# hexbot.net
KiCad netlist of a schematic drawn in Altium Designer
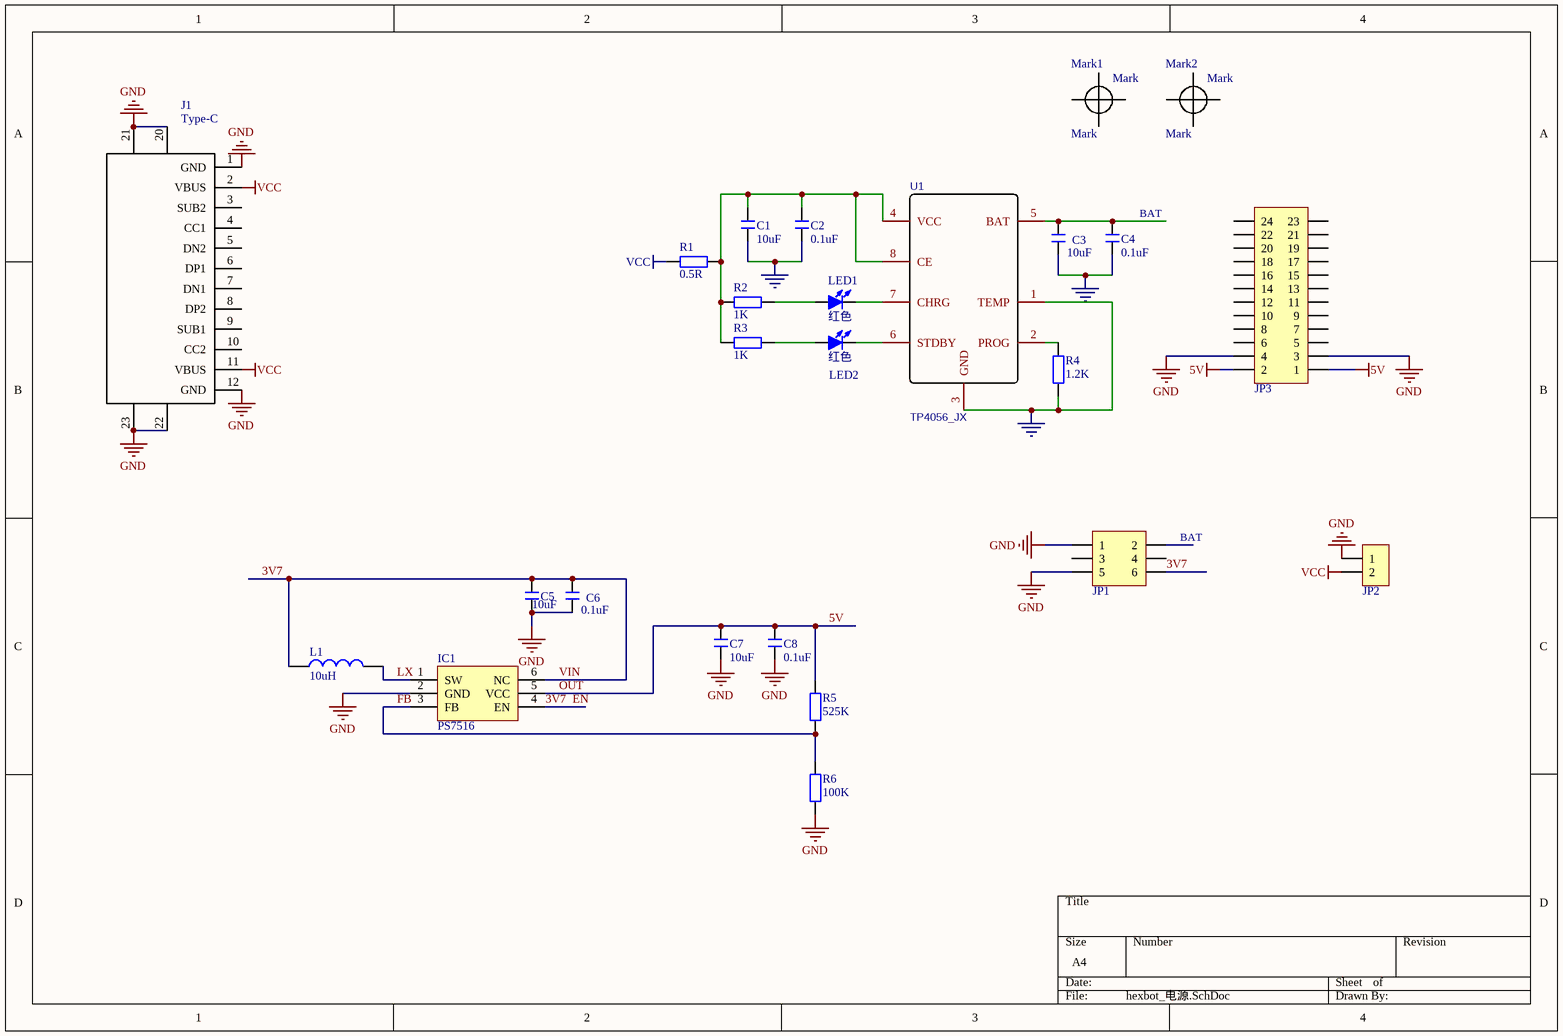
[diagram p0: hexbot_电源.SchDoc]

(export (version "E")
  (design (tool "Eeschema 10.0.6"))
  (components
    (comp (ref "C1")
      (value "10uF")
      (footprint "C 0603_L")
      (description "贴片电容")
      (libsource (lib "0.1 - 电阻-电容-电感") (part "C"))
    )
    (comp (ref "C2")
      (value "0.1uF")
      (footprint "C 0603_L")
      (description "贴片电容")
      (libsource (lib "0.1 - 电阻-电容-电感") (part "C"))
    )
    (comp (ref "C3")
      (value "10uF")
      (footprint "C 0603_L")
      (description "贴片电容")
      (libsource (lib "0.1 - 电阻-电容-电感") (part "C"))
    )
    (comp (ref "C4")
      (value "0.1uF")
      (footprint "C 0603_L")
      (description "贴片电容")
      (libsource (lib "0.1 - 电阻-电容-电感") (part "C"))
    )
    (comp (ref "C5")
      (value "10uF")
      (footprint "C 0603_L")
      (description "贴片电容")
      (libsource (lib "0.1 - 电阻-电容-电感") (part "C"))
    )
    (comp (ref "C6")
      (value "0.1uF")
      (footprint "C 0603_L")
      (description "贴片电容")
      (libsource (lib "0.1 - 电阻-电容-电感") (part "C"))
    )
    (comp (ref "C7")
      (value "10uF")
      (footprint "C 0603_L")
      (description "贴片电容")
      (libsource (lib "0.1 - 电阻-电容-电感") (part "C"))
    )
    (comp (ref "C8")
      (value "0.1uF")
      (footprint "C 0603_L")
      (description "贴片电容")
      (libsource (lib "0.1 - 电阻-电容-电感") (part "C"))
    )
    (comp (ref "IC1")
      (value "PS7516")
      (footprint "SOT23-6L")
      (description "可调升压芯片")
      (fields (field (name "版权归属") "封装库来自淘宝 ID：黄晶宝石"))
      (libsource (lib "1.1 - 电源类芯片") (part "SX1308"))
    )
    (comp (ref "J1")
      (value "Type-C")
      (footprint "Type-C-16")
      (libsource (lib "TYPE-C-16PIN") (part "Type-C-16pin"))
    )
    (comp (ref "JP1")
      (value "Header3X2")
      (footprint "HDR2.54-LI-2x3P")
      (description "3*2P接插件")
      (fields (field (name "版权归属") "封装库来自淘宝 ID：黄晶宝石"))
      (libsource (lib "5.4 - 接插件-脚距2.54 (100mil) ") (part "Header 3X2"))
    )
    (comp (ref "JP2")
      (value "HDR-1X2")
      (footprint "HDR2.54-LI-2P")
      (description "2P接插件")
      (fields (field (name "版权归属") "封装库来自淘宝 ID：黄晶宝石"))
      (libsource (lib "5.4 - 接插件-脚距2.54 (100mil) ") (part "Header 2"))
    )
    (comp (ref "JP3")
      (value "Header 2X11")
      (footprint "HDR2.54-WI-2x12P")
      (description "12*2P接插件")
      (fields (field (name "版权归属") "封装库来自淘宝卖家 ID：黄晶宝石"))
      (libsource (lib "5.4 - 接插件-脚距2.54 (100mil) ") (part "Header 12X2"))
    )
    (comp (ref "L1")
      (value "10uH")
      (footprint "L 0603")
      (description "小功率贴片电感")
      (libsource (lib "0.1 - 电阻-电容-电感") (part "L"))
    )
    (comp (ref "LED1")
      (value "红色")
      (footprint "LED 0603R")
      (description "贴片LED")
      (fields (field (name "版权归属") "封装库来自淘宝 ID：黄晶宝石"))
      (libsource (lib "0.3 - LED发光二极管") (part "LED-SMD"))
    )
    (comp (ref "LED2")
      (value "红色")
      (footprint "LED 0603R")
      (description "贴片LED")
      (fields (field (name "版权归属") "封装库来自淘宝 ID：黄晶宝石"))
      (libsource (lib "0.3 - LED发光二极管") (part "LED-SMD"))
    )
    (comp (ref "Mark1") (value "Mark") (footprint "Mark:Mark") (libsource (lib "Mark") (part "Mark")))
    (comp (ref "Mark2") (value "Mark") (footprint "Mark:Mark") (libsource (lib "Mark") (part "Mark")))
    (comp (ref "R1")
      (value "0.5R")
      (footprint "R 0603_L")
      (description "贴片电阻")
      (fields (field (name "版权归属") "来自淘宝 ID：黄晶宝石"))
      (libsource (lib "0.1 - 电阻-电容-电感") (part "R"))
    )
    (comp (ref "R2")
      (value "1K")
      (footprint "R 0603_L")
      (description "贴片电阻")
      (fields (field (name "版权归属") "来自淘宝 ID：黄晶宝石"))
      (libsource (lib "0.1 - 电阻-电容-电感") (part "R"))
    )
    (comp (ref "R3")
      (value "1K")
      (footprint "R 0603_L")
      (description "贴片电阻")
      (fields (field (name "版权归属") "来自淘宝 ID：黄晶宝石"))
      (libsource (lib "0.1 - 电阻-电容-电感") (part "R"))
    )
    (comp (ref "R4")
      (value "1.2K")
      (footprint "R 0603_L")
      (description "贴片电阻")
      (fields (field (name "版权归属") "来自淘宝 ID：黄晶宝石"))
      (libsource (lib "0.1 - 电阻-电容-电感") (part "R"))
    )
    (comp (ref "R5")
      (value "525K")
      (footprint "R 0805_L")
      (description "贴片电阻")
      (fields (field (name "版权归属") "来自淘宝 ID：黄晶宝石"))
      (libsource (lib "0.1 - 电阻-电容-电感") (part "R"))
    )
    (comp (ref "R6")
      (value "100K")
      (footprint "R 0805_L")
      (description "贴片电阻")
      (fields (field (name "版权归属") "来自淘宝 ID：黄晶宝石"))
      (libsource (lib "0.1 - 电阻-电容-电感") (part "R"))
    )
    (comp (ref "U1") (value "TP4056_JX") (footprint "TP4056") (libsource (lib "TP4056") (part "TP4056_JX")))
  )
  (nets
    (net (code "1") (name "/3V7") (class "Default")
      (node (ref "C5") (pin "2") (pinfunction "2_2") (pintype "passive"))
      (node (ref "C6") (pin "2") (pinfunction "2_2") (pintype "passive"))
      (node (ref "IC1") (pin "4") (pinfunction "EN_4") (pintype "passive"))
      (node (ref "IC1") (pin "6") (pinfunction "NC_6") (pintype "passive"))
      (node (ref "JP1") (pin "6") (pinfunction "6_6") (pintype "passive"))
      (node (ref "L1") (pin "1") (pinfunction "1_1") (pintype "passive"))
    )
    (net (code "2") (name "/BAT") (class "Default")
      (node (ref "C3") (pin "2") (pinfunction "2_2") (pintype "passive"))
      (node (ref "C4") (pin "2") (pinfunction "2_2") (pintype "passive"))
      (node (ref "JP1") (pin "2") (pinfunction "2_2") (pintype "passive"))
      (node (ref "U1") (pin "5") (pinfunction "BAT_5") (pintype "passive"))
    )
    (net (code "3") (name "/FB") (class "Default")
      (node (ref "IC1") (pin "3") (pinfunction "FB_3") (pintype "passive"))
      (node (ref "R5") (pin "1") (pinfunction "1_1") (pintype "passive"))
      (node (ref "R6") (pin "2") (pinfunction "2_2") (pintype "passive"))
    )
    (net (code "4") (name "/LX") (class "Default")
      (node (ref "IC1") (pin "1") (pinfunction "SW_1") (pintype "passive"))
      (node (ref "L1") (pin "2") (pinfunction "2_2") (pintype "passive"))
    )
    (net (code "5") (name "5V") (class "Default")
      (node (ref "C7") (pin "2") (pinfunction "2_2") (pintype "passive"))
      (node (ref "C8") (pin "2") (pinfunction "2_2") (pintype "passive"))
      (node (ref "IC1") (pin "5") (pinfunction "VCC_5") (pintype "passive"))
      (node (ref "JP3") (pin "1") (pinfunction "1_1") (pintype "passive"))
      (node (ref "JP3") (pin "2") (pinfunction "2_2") (pintype "passive"))
      (node (ref "R5") (pin "2") (pinfunction "2_2") (pintype "passive"))
    )
    (net (code "6") (name "GND") (class "Default")
      (node (ref "C1") (pin "1") (pinfunction "1_1") (pintype "passive"))
      (node (ref "C2") (pin "1") (pinfunction "1_1") (pintype "passive"))
      (node (ref "C3") (pin "1") (pinfunction "1_1") (pintype "passive"))
      (node (ref "C4") (pin "1") (pinfunction "1_1") (pintype "passive"))
      (node (ref "C5") (pin "1") (pinfunction "1_1") (pintype "passive"))
      (node (ref "C6") (pin "1") (pinfunction "1_1") (pintype "passive"))
      (node (ref "C7") (pin "1") (pinfunction "1_1") (pintype "passive"))
      (node (ref "C8") (pin "1") (pinfunction "1_1") (pintype "passive"))
      (node (ref "IC1") (pin "2") (pinfunction "GND_2") (pintype "passive"))
      (node (ref "J1") (pin "1") (pinfunction "GND_1") (pintype "passive"))
      (node (ref "J1") (pin "12") (pinfunction "GND_12") (pintype "passive"))
      (node (ref "J1") (pin "20") (pintype "passive"))
      (node (ref "J1") (pin "21") (pintype "passive"))
      (node (ref "J1") (pin "22") (pintype "passive"))
      (node (ref "J1") (pin "23") (pintype "passive"))
      (node (ref "JP1") (pin "1") (pinfunction "1_1") (pintype "passive"))
      (node (ref "JP1") (pin "5") (pinfunction "5_5") (pintype "passive"))
      (node (ref "JP2") (pin "1") (pinfunction "1_1") (pintype "passive"))
      (node (ref "JP3") (pin "3") (pinfunction "3_3") (pintype "passive"))
      (node (ref "JP3") (pin "4") (pinfunction "4_4") (pintype "passive"))
      (node (ref "R4") (pin "1") (pinfunction "1_1") (pintype "passive"))
      (node (ref "R6") (pin "1") (pinfunction "1_1") (pintype "passive"))
      (node (ref "U1") (pin "1") (pinfunction "TEMP_1") (pintype "passive"))
      (node (ref "U1") (pin "3") (pinfunction "GND_3") (pintype "passive"))
    )
    (net (code "7") (name "Net-(LED1-A)") (class "Default")
      (node (ref "LED1") (pin "1") (pinfunction "A_1") (pintype "passive"))
      (node (ref "R2") (pin "2") (pinfunction "2_2") (pintype "passive"))
    )
    (net (code "8") (name "Net-(LED1-K)") (class "Default")
      (node (ref "LED1") (pin "2") (pinfunction "K_2") (pintype "passive"))
      (node (ref "U1") (pin "7") (pinfunction "CHRG_7") (pintype "passive"))
    )
    (net (code "9") (name "Net-(LED2-A)") (class "Default")
      (node (ref "LED2") (pin "1") (pinfunction "A_1") (pintype "passive"))
      (node (ref "R3") (pin "2") (pinfunction "2_2") (pintype "passive"))
    )
    (net (code "10") (name "Net-(LED2-K)") (class "Default")
      (node (ref "LED2") (pin "2") (pinfunction "K_2") (pintype "passive"))
      (node (ref "U1") (pin "6") (pinfunction "STDBY_6") (pintype "passive"))
    )
    (net (code "11") (name "Net-(U1-CE)") (class "Default")
      (node (ref "C1") (pin "2") (pinfunction "2_2") (pintype "passive"))
      (node (ref "C2") (pin "2") (pinfunction "2_2") (pintype "passive"))
      (node (ref "R1") (pin "2") (pinfunction "2_2") (pintype "passive"))
      (node (ref "R2") (pin "1") (pinfunction "1_1") (pintype "passive"))
      (node (ref "R3") (pin "1") (pinfunction "1_1") (pintype "passive"))
      (node (ref "U1") (pin "4") (pinfunction "VCC_4") (pintype "passive"))
      (node (ref "U1") (pin "8") (pinfunction "CE_8") (pintype "passive"))
    )
    (net (code "12") (name "Net-(U1-PROG)") (class "Default")
      (node (ref "R4") (pin "2") (pinfunction "2_2") (pintype "passive"))
      (node (ref "U1") (pin "2") (pinfunction "PROG_2") (pintype "passive"))
    )
    (net (code "13") (name "VCC") (class "Default")
      (node (ref "J1") (pin "11") (pinfunction "VBUS_11") (pintype "passive"))
      (node (ref "J1") (pin "2") (pinfunction "VBUS_2") (pintype "passive"))
      (node (ref "JP2") (pin "2") (pinfunction "2_2") (pintype "passive"))
      (node (ref "R1") (pin "1") (pinfunction "1_1") (pintype "passive"))
    )
    (net (code "14") (name "unconnected-(J1-CC1-Pad4)") (class "Default")
      (node (ref "J1") (pin "4") (pinfunction "CC1_4") (pintype "passive"))
    )
    (net (code "15") (name "unconnected-(J1-CC2-Pad10)") (class "Default")
      (node (ref "J1") (pin "10") (pinfunction "CC2_10") (pintype "passive"))
    )
    (net (code "16") (name "unconnected-(J1-DN1-Pad7)") (class "Default")
      (node (ref "J1") (pin "7") (pinfunction "DN1_7") (pintype "passive"))
    )
    (net (code "17") (name "unconnected-(J1-DN2-Pad5)") (class "Default")
      (node (ref "J1") (pin "5") (pinfunction "DN2_5") (pintype "passive"))
    )
    (net (code "18") (name "unconnected-(J1-DP1-Pad6)") (class "Default")
      (node (ref "J1") (pin "6") (pinfunction "DP1_6") (pintype "passive"))
    )
    (net (code "19") (name "unconnected-(J1-DP2-Pad8)") (class "Default")
      (node (ref "J1") (pin "8") (pinfunction "DP2_8") (pintype "passive"))
    )
    (net (code "20") (name "unconnected-(J1-SUB1-Pad9)") (class "Default")
      (node (ref "J1") (pin "9") (pinfunction "SUB1_9") (pintype "passive"))
    )
    (net (code "21") (name "unconnected-(J1-SUB2-Pad3)") (class "Default")
      (node (ref "J1") (pin "3") (pinfunction "SUB2_3") (pintype "passive"))
    )
    (net (code "22") (name "unconnected-(JP1-Pad3)") (class "Default")
      (node (ref "JP1") (pin "3") (pinfunction "3_3") (pintype "passive"))
    )
    (net (code "23") (name "unconnected-(JP1-Pad4)") (class "Default")
      (node (ref "JP1") (pin "4") (pinfunction "4_4") (pintype "passive"))
    )
    (net (code "24") (name "unconnected-(JP3-Pad5)") (class "Default")
      (node (ref "JP3") (pin "5") (pinfunction "5_5") (pintype "passive"))
    )
    (net (code "25") (name "unconnected-(JP3-Pad6)") (class "Default")
      (node (ref "JP3") (pin "6") (pinfunction "6_6") (pintype "passive"))
    )
    (net (code "26") (name "unconnected-(JP3-Pad7)") (class "Default")
      (node (ref "JP3") (pin "7") (pinfunction "7_7") (pintype "passive"))
    )
    (net (code "27") (name "unconnected-(JP3-Pad8)") (class "Default")
      (node (ref "JP3") (pin "8") (pinfunction "8_8") (pintype "passive"))
    )
    (net (code "28") (name "unconnected-(JP3-Pad9)") (class "Default")
      (node (ref "JP3") (pin "9") (pinfunction "9_9") (pintype "passive"))
    )
    (net (code "29") (name "unconnected-(JP3-Pad10)") (class "Default")
      (node (ref "JP3") (pin "10") (pinfunction "10_10") (pintype "passive"))
    )
    (net (code "30") (name "unconnected-(JP3-Pad11)") (class "Default")
      (node (ref "JP3") (pin "11") (pinfunction "11_11") (pintype "passive"))
    )
    (net (code "31") (name "unconnected-(JP3-Pad12)") (class "Default")
      (node (ref "JP3") (pin "12") (pinfunction "12_12") (pintype "passive"))
    )
    (net (code "32") (name "unconnected-(JP3-Pad13)") (class "Default")
      (node (ref "JP3") (pin "13") (pinfunction "13_13") (pintype "passive"))
    )
    (net (code "33") (name "unconnected-(JP3-Pad14)") (class "Default")
      (node (ref "JP3") (pin "14") (pinfunction "14_14") (pintype "passive"))
    )
    (net (code "34") (name "unconnected-(JP3-Pad15)") (class "Default")
      (node (ref "JP3") (pin "15") (pinfunction "15_15") (pintype "passive"))
    )
    (net (code "35") (name "unconnected-(JP3-Pad16)") (class "Default")
      (node (ref "JP3") (pin "16") (pinfunction "16_16") (pintype "passive"))
    )
    (net (code "36") (name "unconnected-(JP3-Pad17)") (class "Default")
      (node (ref "JP3") (pin "17") (pinfunction "17_17") (pintype "passive"))
    )
    (net (code "37") (name "unconnected-(JP3-Pad18)") (class "Default")
      (node (ref "JP3") (pin "18") (pinfunction "18_18") (pintype "passive"))
    )
    (net (code "38") (name "unconnected-(JP3-Pad19)") (class "Default")
      (node (ref "JP3") (pin "19") (pinfunction "19_19") (pintype "passive"))
    )
    (net (code "39") (name "unconnected-(JP3-Pad20)") (class "Default")
      (node (ref "JP3") (pin "20") (pinfunction "20_20") (pintype "passive"))
    )
    (net (code "40") (name "unconnected-(JP3-Pad21)") (class "Default")
      (node (ref "JP3") (pin "21") (pinfunction "21_21") (pintype "passive"))
    )
    (net (code "41") (name "unconnected-(JP3-Pad22)") (class "Default")
      (node (ref "JP3") (pin "22") (pinfunction "22_22") (pintype "passive"))
    )
    (net (code "42") (name "unconnected-(JP3-Pad23)") (class "Default")
      (node (ref "JP3") (pin "23") (pinfunction "23_23") (pintype "passive"))
    )
    (net (code "43") (name "unconnected-(JP3-Pad24)") (class "Default")
      (node (ref "JP3") (pin "24") (pinfunction "24_24") (pintype "passive"))
    )
  )
)
